# 01_MCU.net
KiCad netlist of a schematic drawn in Altium Designer
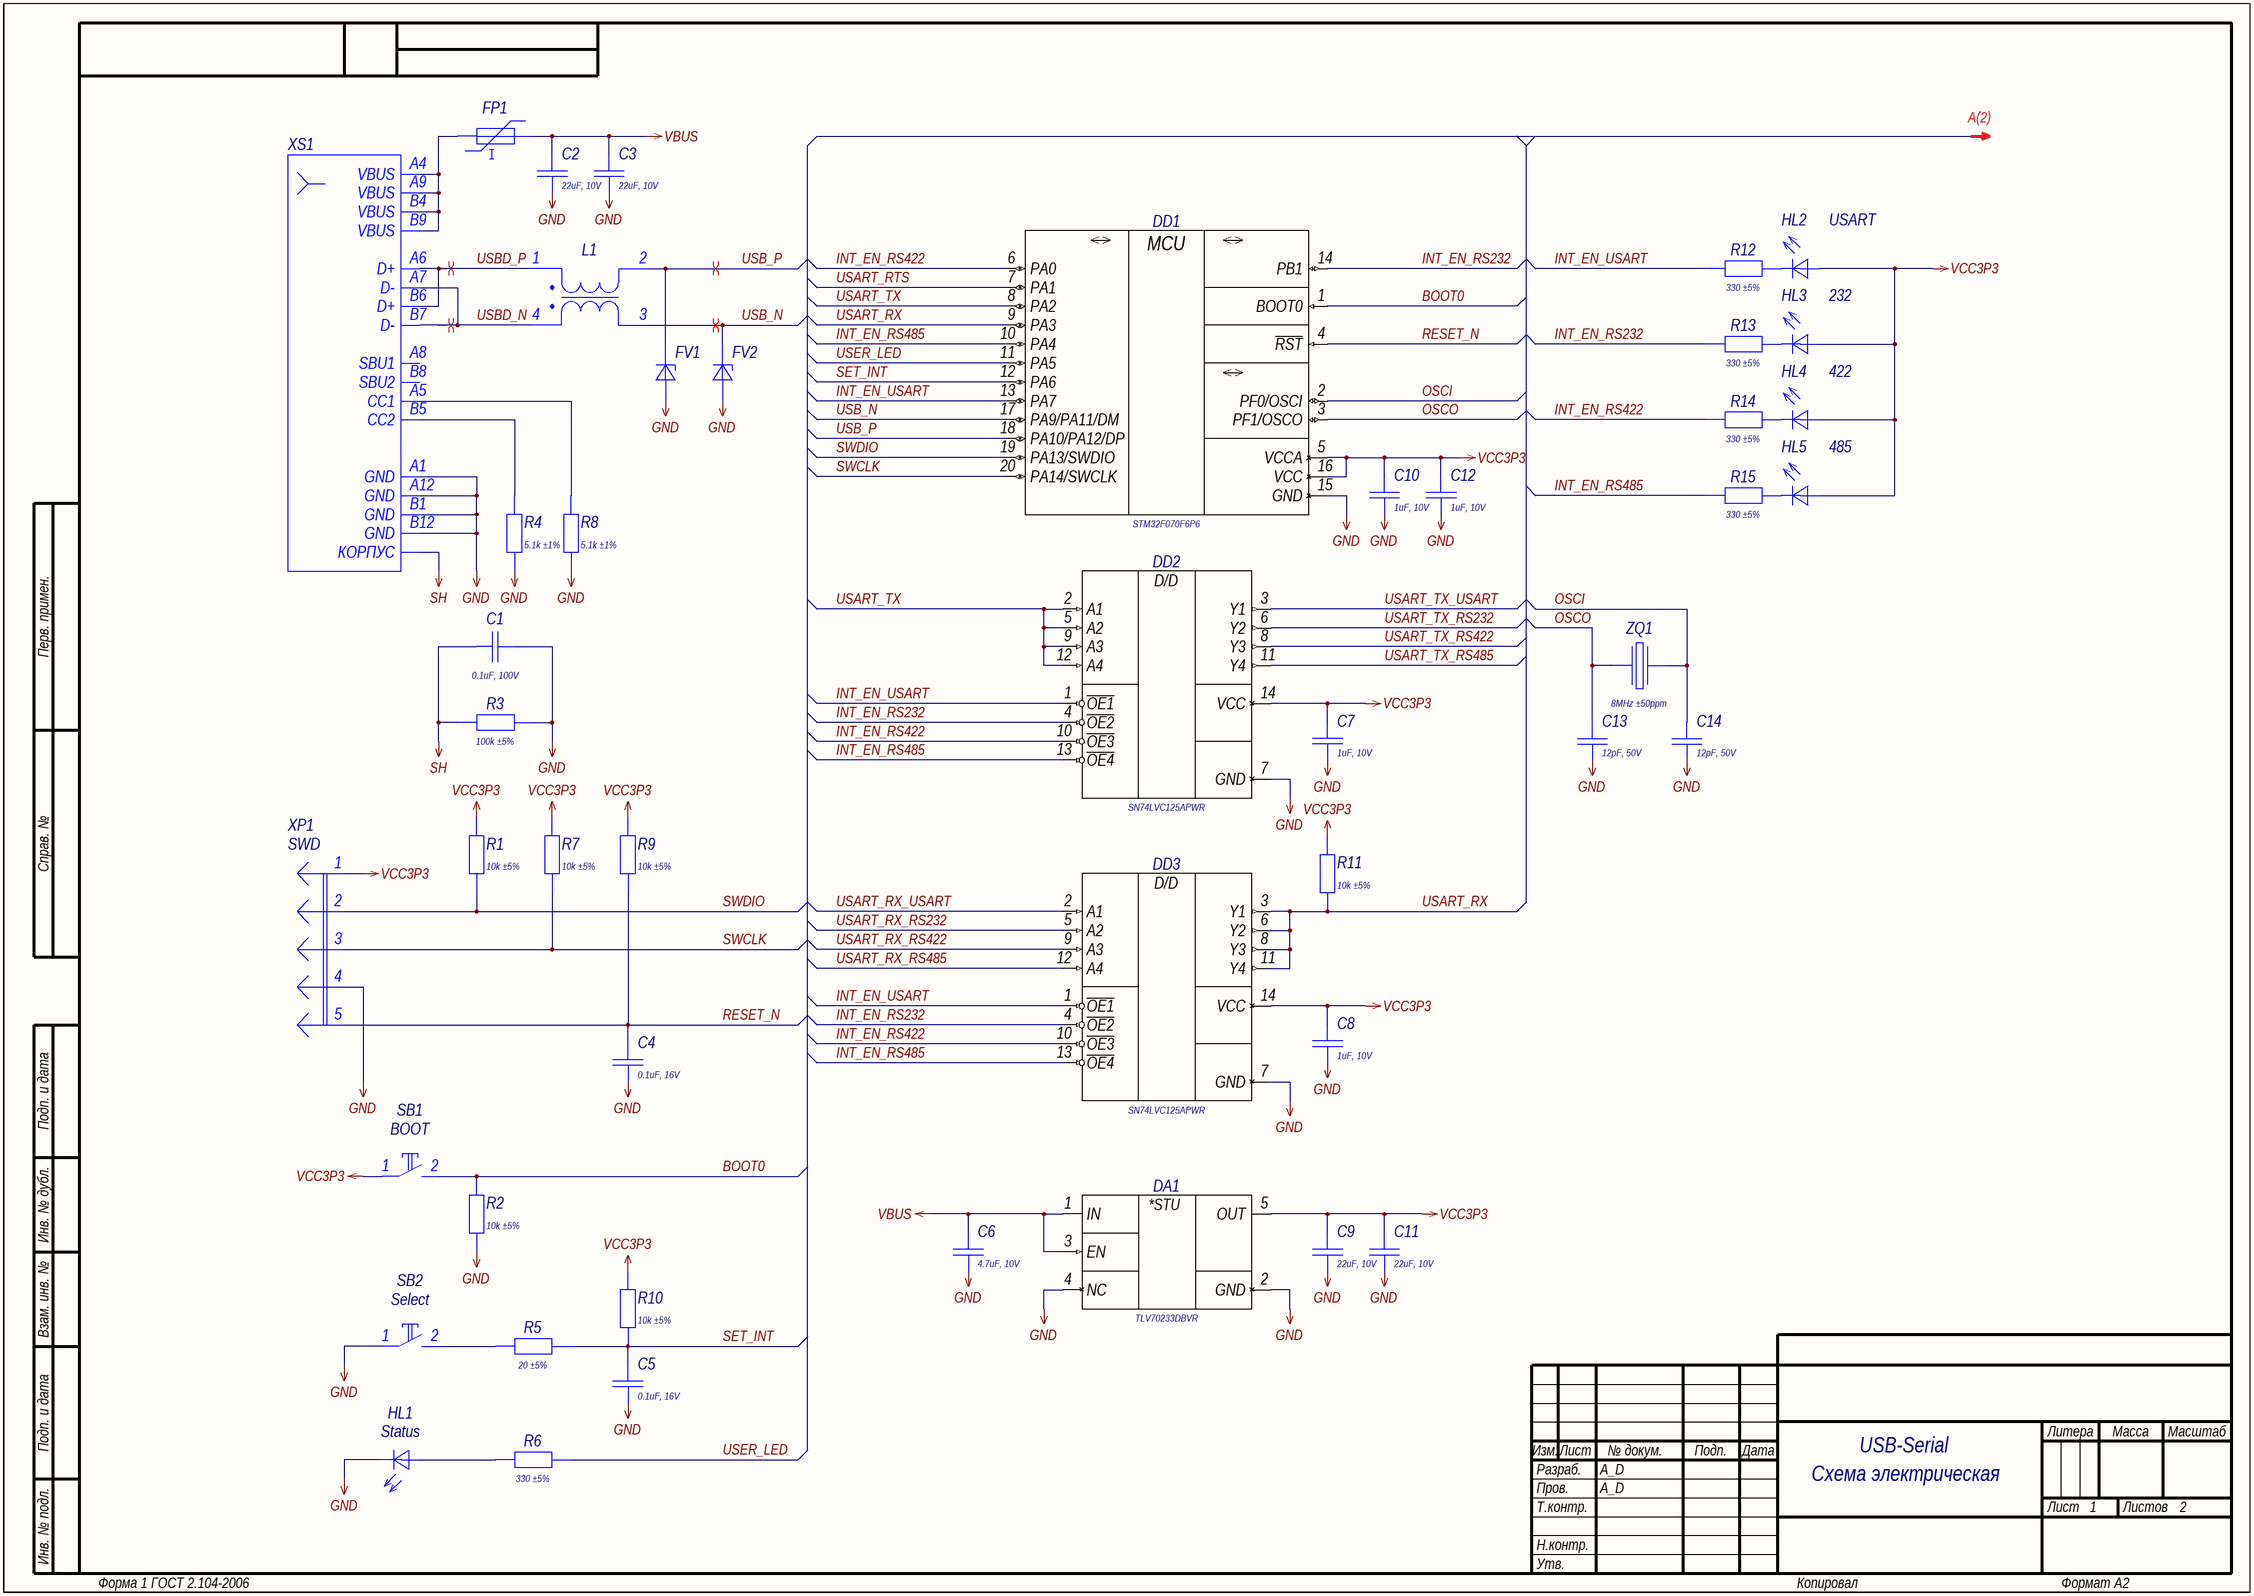
[diagram p0: 01_MCU.SchDoc]

(export (version "E")
  (design (tool "Eeschema 10.0.6"))
  (components
    (comp (ref "C1")
      (value "Capacitor")
      (footprint "C0603_160X080H080_H")
      (fields
        (field (name "SCHEMATIC VALUE") "0.1uF, 100V")
        (field (name "PART NUMBER") "GRM188R72A104KA35D")
        (field (name "VOLTAGE") "100V")
        (field (name "TOLERANCE") "±10%")
        (field (name "PUBLISHER") "Andrew Danich")
      )
      (libsource (lib "ADLib") (part "Capacitor"))
    )
    (comp (ref "C2")
      (value "Capacitor")
      (footprint "C0603_160X080H080_H")
      (fields
        (field (name "SCHEMATIC VALUE") "22uF, 10V")
        (field (name "PART NUMBER") "GRM188R61A226ME15D")
        (field (name "VOLTAGE") "10V")
        (field (name "TOLERANCE") "±20%")
        (field (name "PUBLISHER") "Andrew Danich")
      )
      (libsource (lib "ADLib") (part "Capacitor"))
    )
    (comp (ref "C3")
      (value "Capacitor")
      (footprint "C0603_160X080H080_H")
      (fields
        (field (name "SCHEMATIC VALUE") "22uF, 10V")
        (field (name "PART NUMBER") "GRM188R61A226ME15D")
        (field (name "VOLTAGE") "10V")
        (field (name "TOLERANCE") "±20%")
        (field (name "PUBLISHER") "Andrew Danich")
      )
      (libsource (lib "ADLib") (part "Capacitor"))
    )
    (comp (ref "C4")
      (value "Capacitor")
      (footprint "C0402_100X050H050_H")
      (fields
        (field (name "SCHEMATIC VALUE") "0.1uF, 16V")
        (field (name "PART NUMBER") "GCM155R71C104KA55D")
        (field (name "VOLTAGE") "16V")
        (field (name "TOLERANCE") "±10%")
        (field (name "PUBLISHER") "Andrew Danich")
      )
      (libsource (lib "ADLib") (part "Capacitor"))
    )
    (comp (ref "C5")
      (value "Capacitor")
      (footprint "C0402_100X050H050_H")
      (fields
        (field (name "SCHEMATIC VALUE") "0.1uF, 16V")
        (field (name "PART NUMBER") "GCM155R71C104KA55D")
        (field (name "VOLTAGE") "16V")
        (field (name "TOLERANCE") "±10%")
        (field (name "PUBLISHER") "Andrew Danich")
      )
      (libsource (lib "ADLib") (part "Capacitor"))
    )
    (comp (ref "C6")
      (value "Capacitor")
      (footprint "C0402_100X050H050_H")
      (fields
        (field (name "SCHEMATIC VALUE") "4.7uF, 10V")
        (field (name "PART NUMBER") "GRM155R61A475MEAAD")
        (field (name "VOLTAGE") "10V")
        (field (name "TOLERANCE") "±20%")
        (field (name "PUBLISHER") "Andrew Danich")
      )
      (libsource (lib "ADLib") (part "Capacitor"))
    )
    (comp (ref "C7")
      (value "Capacitor")
      (footprint "C0402_100X050H050_H")
      (fields
        (field (name "SCHEMATIC VALUE") "1uF, 10V")
        (field (name "PART NUMBER") "GRM155C71A105KE11D")
        (field (name "VOLTAGE") "10V")
        (field (name "TOLERANCE") "±10%")
        (field (name "PUBLISHER") "Andrew Danich")
      )
      (libsource (lib "ADLib") (part "Capacitor"))
    )
    (comp (ref "C8")
      (value "Capacitor")
      (footprint "C0402_100X050H050_H")
      (fields
        (field (name "SCHEMATIC VALUE") "1uF, 10V")
        (field (name "PART NUMBER") "GRM155C71A105KE11D")
        (field (name "VOLTAGE") "10V")
        (field (name "TOLERANCE") "±10%")
        (field (name "PUBLISHER") "Andrew Danich")
      )
      (libsource (lib "ADLib") (part "Capacitor"))
    )
    (comp (ref "C9")
      (value "Capacitor")
      (footprint "C0603_160X080H080_H")
      (fields
        (field (name "SCHEMATIC VALUE") "22uF, 10V")
        (field (name "PART NUMBER") "GRM188R61A226ME15D")
        (field (name "VOLTAGE") "10V")
        (field (name "TOLERANCE") "±20%")
        (field (name "PUBLISHER") "Andrew Danich")
      )
      (libsource (lib "ADLib") (part "Capacitor"))
    )
    (comp (ref "C10")
      (value "Capacitor")
      (footprint "C0402_100X050H050_H")
      (fields
        (field (name "SCHEMATIC VALUE") "1uF, 10V")
        (field (name "PART NUMBER") "GRM155C71A105KE11D")
        (field (name "VOLTAGE") "10V")
        (field (name "TOLERANCE") "±10%")
        (field (name "PUBLISHER") "Andrew Danich")
      )
      (libsource (lib "ADLib") (part "Capacitor"))
    )
    (comp (ref "C11")
      (value "Capacitor")
      (footprint "C0603_160X080H080_H")
      (fields
        (field (name "SCHEMATIC VALUE") "22uF, 10V")
        (field (name "PART NUMBER") "GRM188R61A226ME15D")
        (field (name "VOLTAGE") "10V")
        (field (name "TOLERANCE") "±20%")
        (field (name "PUBLISHER") "Andrew Danich")
      )
      (libsource (lib "ADLib") (part "Capacitor"))
    )
    (comp (ref "C12")
      (value "Capacitor")
      (footprint "C0402_100X050H050_H")
      (fields
        (field (name "SCHEMATIC VALUE") "1uF, 10V")
        (field (name "PART NUMBER") "GRM155C71A105KE11D")
        (field (name "VOLTAGE") "10V")
        (field (name "TOLERANCE") "±10%")
        (field (name "PUBLISHER") "Andrew Danich")
      )
      (libsource (lib "ADLib") (part "Capacitor"))
    )
    (comp (ref "C13")
      (value "Capacitor")
      (footprint "C0402_100X050H050_H")
      (fields
        (field (name "SCHEMATIC VALUE") "12pF, 50V")
        (field (name "PART NUMBER") "GRM1555C1H120JA01D")
        (field (name "VOLTAGE") "50V")
        (field (name "TOLERANCE") "±5%")
        (field (name "PUBLISHER") "Andrew Danich")
      )
      (libsource (lib "ADLib") (part "Capacitor"))
    )
    (comp (ref "C14")
      (value "Capacitor")
      (footprint "C0402_100X050H050_H")
      (fields
        (field (name "SCHEMATIC VALUE") "12pF, 50V")
        (field (name "PART NUMBER") "GRM1555C1H120JA01D")
        (field (name "VOLTAGE") "50V")
        (field (name "TOLERANCE") "±5%")
        (field (name "PUBLISHER") "Andrew Danich")
      )
      (libsource (lib "ADLib") (part "Capacitor"))
    )
    (comp (ref "DA1")
      (value "TLV702xxPDBV-Series")
      (footprint "SOT-23-5_095P290X160X145_N")
      (fields
        (field (name "SCHEMATIC VALUE") "TLV70233DBVR")
        (field (name "PART NUMBER") "TLV70233DBVR")
        (field (name "LCSC PART") "C26833")
        (field (name "MANUFACTURER") "Texas Instruments")
        (field (name "PUBLISHER") "Andrew Danich")
      )
      (libsource (lib "ADLib") (part "TLV702xxPDBV-Series"))
    )
    (comp (ref "DD1")
      (value "STM32F070FxPx-Series")
      (footprint "TSSOP-20_065P650X440X120_N")
      (fields
        (field (name "SCHEMATIC VALUE") "STM32F070F6P6")
        (field (name "PART NUMBER") "STM32F070F6P6")
        (field (name "MANUFACTURER") "STMicroelectronics")
        (field (name "PUBLISHER") "Andrew Danich")
      )
      (libsource (lib "ADLib") (part "STM32F070FxPx-Series"))
    )
    (comp (ref "DD2")
      (value "SN74LVC125APW")
      (footprint "TSSOP-14_065P500X440X120_N")
      (fields
        (field (name "SCHEMATIC VALUE") "SN74LVC125APWR")
        (field (name "PART NUMBER") "SN74LVC125APWR")
        (field (name "LCSC PART") "C7813")
        (field (name "MANUFACTURER") "Texas Instruments")
        (field (name "PUBLISHER") "Andrew Danich")
      )
      (libsource (lib "ADLib") (part "SN74LVC125APW"))
    )
    (comp (ref "DD3")
      (value "SN74LVC125APW")
      (footprint "TSSOP-14_065P500X440X120_N")
      (fields
        (field (name "SCHEMATIC VALUE") "SN74LVC125APWR")
        (field (name "PART NUMBER") "SN74LVC125APWR")
        (field (name "LCSC PART") "C7813")
        (field (name "MANUFACTURER") "Texas Instruments")
        (field (name "PUBLISHER") "Andrew Danich")
      )
      (libsource (lib "ADLib") (part "SN74LVC125APW"))
    )
    (comp (ref "FP1")
      (value "Fuse_PTC")
      (footprint "F0603_160X080H075_H")
      (fields (field (name "PART NUMBER") "0603L100SLYR") (field (name "MANUFACTURER") "Littelfuse"))
      (libsource (lib "ADLib") (part "Fuse_PTC"))
    )
    (comp (ref "FV1")
      (value "Suppressor_21")
      (footprint "X1-DFN1006-2_070P060X100X050_N")
      (fields
        (field (name "PART NUMBER") "PESDUC2FD5VU")
        (field (name "LCSC PART") "C496534")
        (field (name "MANUFACTURER") "Shanghai Prisemi Elec")
        (field (name "PUBLISHER") "Andrew Danich")
      )
      (libsource (lib "ADLib") (part "Suppressor_21"))
    )
    (comp (ref "FV2")
      (value "Suppressor_21")
      (footprint "X1-DFN1006-2_070P060X100X050_N")
      (fields
        (field (name "PART NUMBER") "PESDUC2FD5VU")
        (field (name "LCSC PART") "C496534")
        (field (name "MANUFACTURER") "Shanghai Prisemi Elec")
        (field (name "PUBLISHER") "Andrew Danich")
      )
      (libsource (lib "ADLib") (part "Suppressor_21"))
    )
    (comp (ref "HL1")
      (value "Status")
      (footprint "LD0603_L")
      (fields
        (field (name "PART NUMBER") "NCD0603G1")
        (field (name "MANUFACTURER") "Foshan NationStar Optoelectronics")
        (field (name "LCSC PART") "C84267")
        (field (name "PUBLISHER") "Andrew Danich")
      )
      (libsource (lib "ADLib") (part "Led-1"))
    )
    (comp (ref "HL2")
      (value "USART")
      (footprint "LD0603_L")
      (fields
        (field (name "PART NUMBER") "NCD0603W1")
        (field (name "MANUFACTURER") "Foshan NationStar Optoelectronics")
        (field (name "LCSC PART") "C84265")
        (field (name "PUBLISHER") "Andrew Danich")
      )
      (libsource (lib "ADLib") (part "Led-1"))
    )
    (comp (ref "HL3")
      (value "232")
      (footprint "LD0603_L")
      (fields
        (field (name "PART NUMBER") "NCD0603W1")
        (field (name "MANUFACTURER") "Foshan NationStar Optoelectronics")
        (field (name "LCSC PART") "C84265")
        (field (name "PUBLISHER") "Andrew Danich")
      )
      (libsource (lib "ADLib") (part "Led-1"))
    )
    (comp (ref "HL4")
      (value "422")
      (footprint "LD0603_L")
      (fields
        (field (name "PART NUMBER") "NCD0603W1")
        (field (name "MANUFACTURER") "Foshan NationStar Optoelectronics")
        (field (name "LCSC PART") "C84265")
        (field (name "PUBLISHER") "Andrew Danich")
      )
      (libsource (lib "ADLib") (part "Led-1"))
    )
    (comp (ref "HL5")
      (value "485")
      (footprint "LD0603_L")
      (fields
        (field (name "PART NUMBER") "NCD0603W1")
        (field (name "MANUFACTURER") "Foshan NationStar Optoelectronics")
        (field (name "LCSC PART") "C84265")
        (field (name "PUBLISHER") "Andrew Danich")
      )
      (libsource (lib "ADLib") (part "Led-1"))
    )
    (comp (ref "L1")
      (value "Coil-2xCommon_H")
      (footprint "DLW21HN-Series")
      (fields
        (field (name "PART NUMBER") "DLW21HN121SQ2L")
        (field (name "MANUFACTURER") "Murata")
        (field (name "PUBLISHER") "Andrew Danich")
      )
      (libsource (lib "ADLib") (part "Coil-2xCommon_H"))
    )
    (comp (ref "R1")
      (value "Resistor")
      (footprint "R0402_100X050H035_H")
      (fields
        (field (name "SCHEMATIC VALUE") "10k ±5%")
        (field (name "PART NUMBER") "RC0402JR-0710KL")
        (field (name "TOLERANCE") "±5%")
        (field (name "MANUFACTURER") "Yageo")
        (field (name "PUBLISHER") "Andrew Danich")
      )
      (libsource (lib "ADLib") (part "Resistor"))
    )
    (comp (ref "R2")
      (value "Resistor")
      (footprint "R0402_100X050H035_H")
      (fields
        (field (name "SCHEMATIC VALUE") "10k ±5%")
        (field (name "PART NUMBER") "RC0402JR-0710KL")
        (field (name "TOLERANCE") "±5%")
        (field (name "MANUFACTURER") "Yageo")
        (field (name "PUBLISHER") "Andrew Danich")
      )
      (libsource (lib "ADLib") (part "Resistor"))
    )
    (comp (ref "R3")
      (value "Resistor")
      (footprint "R0402_100X050H035_H")
      (fields
        (field (name "SCHEMATIC VALUE") "100k ±5%")
        (field (name "PART NUMBER") "RC0402JR-07100KL")
        (field (name "TOLERANCE") "±5%")
        (field (name "MANUFACTURER") "Yageo")
        (field (name "PUBLISHER") "Andrew Danich")
      )
      (libsource (lib "ADLib") (part "Resistor"))
    )
    (comp (ref "R4")
      (value "Resistor")
      (footprint "R0402_100X050H035_H")
      (fields
        (field (name "SCHEMATIC VALUE") "5.1k ±1%")
        (field (name "PART NUMBER") "RC0402FR-075K1L")
        (field (name "TOLERANCE") "±1%")
        (field (name "MANUFACTURER") "Yageo")
        (field (name "PUBLISHER") "Andrew Danich")
      )
      (libsource (lib "ADLib") (part "Resistor"))
    )
    (comp (ref "R5")
      (value "Resistor")
      (footprint "R0402_100X050H035_H")
      (fields
        (field (name "SCHEMATIC VALUE") "20 ±5%")
        (field (name "PART NUMBER") "RC0402JR-0720RL")
        (field (name "TOLERANCE") "±5%")
        (field (name "MANUFACTURER") "Yageo")
        (field (name "PUBLISHER") "Andrew Danich")
      )
      (libsource (lib "ADLib") (part "Resistor"))
    )
    (comp (ref "R6")
      (value "Resistor")
      (footprint "R0402_100X050H035_H")
      (fields
        (field (name "SCHEMATIC VALUE") "330 ±5%")
        (field (name "PART NUMBER") "RC0402JR-07330RL")
        (field (name "TOLERANCE") "±5%")
        (field (name "MANUFACTURER") "Yageo")
        (field (name "PUBLISHER") "Andrew Danich")
      )
      (libsource (lib "ADLib") (part "Resistor"))
    )
    (comp (ref "R7")
      (value "Resistor")
      (footprint "R0402_100X050H035_H")
      (fields
        (field (name "SCHEMATIC VALUE") "10k ±5%")
        (field (name "PART NUMBER") "RC0402JR-0710KL")
        (field (name "TOLERANCE") "±5%")
        (field (name "MANUFACTURER") "Yageo")
        (field (name "PUBLISHER") "Andrew Danich")
      )
      (libsource (lib "ADLib") (part "Resistor"))
    )
    (comp (ref "R8")
      (value "Resistor")
      (footprint "R0402_100X050H035_H")
      (fields
        (field (name "SCHEMATIC VALUE") "5.1k ±1%")
        (field (name "PART NUMBER") "RC0402FR-075K1L")
        (field (name "TOLERANCE") "±1%")
        (field (name "MANUFACTURER") "Yageo")
        (field (name "PUBLISHER") "Andrew Danich")
      )
      (libsource (lib "ADLib") (part "Resistor"))
    )
    (comp (ref "R9")
      (value "Resistor")
      (footprint "R0402_100X050H035_H")
      (fields
        (field (name "SCHEMATIC VALUE") "10k ±5%")
        (field (name "PART NUMBER") "RC0402JR-0710KL")
        (field (name "TOLERANCE") "±5%")
        (field (name "MANUFACTURER") "Yageo")
        (field (name "PUBLISHER") "Andrew Danich")
      )
      (libsource (lib "ADLib") (part "Resistor"))
    )
    (comp (ref "R10")
      (value "Resistor")
      (footprint "R0402_100X050H035_H")
      (fields
        (field (name "SCHEMATIC VALUE") "10k ±5%")
        (field (name "PART NUMBER") "RC0402JR-0710KL")
        (field (name "TOLERANCE") "±5%")
        (field (name "MANUFACTURER") "Yageo")
        (field (name "PUBLISHER") "Andrew Danich")
      )
      (libsource (lib "ADLib") (part "Resistor"))
    )
    (comp (ref "R11")
      (value "Resistor")
      (footprint "R0402_100X050H035_H")
      (fields
        (field (name "SCHEMATIC VALUE") "10k ±5%")
        (field (name "PART NUMBER") "RC0402JR-0710KL")
        (field (name "TOLERANCE") "±5%")
        (field (name "MANUFACTURER") "Yageo")
        (field (name "PUBLISHER") "Andrew Danich")
      )
      (libsource (lib "ADLib") (part "Resistor"))
    )
    (comp (ref "R12")
      (value "Resistor")
      (footprint "R0402_100X050H035_H")
      (fields
        (field (name "SCHEMATIC VALUE") "330 ±5%")
        (field (name "PART NUMBER") "RC0402JR-07330RL")
        (field (name "TOLERANCE") "±5%")
        (field (name "MANUFACTURER") "Yageo")
        (field (name "PUBLISHER") "Andrew Danich")
      )
      (libsource (lib "ADLib") (part "Resistor"))
    )
    (comp (ref "R13")
      (value "Resistor")
      (footprint "R0402_100X050H035_H")
      (fields
        (field (name "SCHEMATIC VALUE") "330 ±5%")
        (field (name "PART NUMBER") "RC0402JR-07330RL")
        (field (name "TOLERANCE") "±5%")
        (field (name "MANUFACTURER") "Yageo")
        (field (name "PUBLISHER") "Andrew Danich")
      )
      (libsource (lib "ADLib") (part "Resistor"))
    )
    (comp (ref "R14")
      (value "Resistor")
      (footprint "R0402_100X050H035_H")
      (fields
        (field (name "SCHEMATIC VALUE") "330 ±5%")
        (field (name "PART NUMBER") "RC0402JR-07330RL")
        (field (name "TOLERANCE") "±5%")
        (field (name "MANUFACTURER") "Yageo")
        (field (name "PUBLISHER") "Andrew Danich")
      )
      (libsource (lib "ADLib") (part "Resistor"))
    )
    (comp (ref "R15")
      (value "Resistor")
      (footprint "R0402_100X050H035_H")
      (fields
        (field (name "SCHEMATIC VALUE") "330 ±5%")
        (field (name "PART NUMBER") "RC0402JR-07330RL")
        (field (name "TOLERANCE") "±5%")
        (field (name "MANUFACTURER") "Yageo")
        (field (name "PUBLISHER") "Andrew Danich")
      )
      (libsource (lib "ADLib") (part "Resistor"))
    )
    (comp (ref "SB1")
      (value "BOOT")
      (footprint "IT-1185AP")
      (fields (field (name "PART NUMBER") "IT-1185AP") (field (name "PUBLISHER") "Andrew Danich"))
      (libsource (lib "ADLib") (part "BT-01x-01p"))
    )
    (comp (ref "SB2")
      (value "Select")
      (footprint "IT-1185AP")
      (fields (field (name "PART NUMBER") "IT-1185AP") (field (name "PUBLISHER") "Andrew Danich"))
      (libsource (lib "ADLib") (part "BT-01x-01p"))
    )
    (comp (ref "XP1")
      (value "SWD")
      (footprint "PLS-5")
      (fields (field (name "PART NUMBER") "PLS-5") (field (name "PUBLISHER") "Andrew Danich"))
      (libsource (lib "ADLib") (part "Con-5-M"))
    )
    (comp (ref "XS1")
      (value "Text")
      (footprint "U262-161N-4BVC11")
      (fields
        (field (name "PART NUMBER") "U262-161N-4BVC11")
        (field (name "MANUFACTURER") "XKB Enterprise")
        (field (name "PUBLISHER") "Andrew Danich")
      )
      (libsource (lib "ADLib") (part "Con-USB_C-F-16P"))
    )
    (comp (ref "ZQ1")
      (value "Crystal")
      (footprint "SMD 5x3.2mm")
      (fields
        (field (name "SCHEMATIC VALUE") "8MHz ±50ppm")
        (field (name "PART NUMBER") "KX-9A 8.0 MHz 30/50/100 16 pF")
        (field (name "MANUFACTURER") "Geyer")
        (field (name "PUBLISHER") "Andrew Danich")
      )
      (libsource (lib "ADLib") (part "Crystal"))
    )
  )
  (nets
    (net (code "1") (name "/BOOT0") (class "Default")
      (node (ref "DD1") (pin "1") (pinfunction "BOOT0_1") (pintype "input"))
      (node (ref "R2") (pin "2") (pinfunction "2_2") (pintype "passive"))
      (node (ref "SB1") (pin "2") (pintype "passive"))
    )
    (net (code "2") (name "/INT_EN_RS232") (class "Default")
      (node (ref "DD1") (pin "14") (pinfunction "PB1_14") (pintype "bidirectional"))
      (node (ref "DD2") (pin "4") (pinfunction "~{OE2}_4") (pintype "input"))
      (node (ref "DD3") (pin "4") (pinfunction "~{OE2}_4") (pintype "input"))
      (node (ref "R13") (pin "2") (pinfunction "2_2") (pintype "passive"))
    )
    (net (code "3") (name "/INT_EN_RS422") (class "Default")
      (node (ref "DD1") (pin "6") (pinfunction "PA0_6") (pintype "bidirectional"))
      (node (ref "DD2") (pin "10") (pinfunction "~{OE3}_10") (pintype "input"))
      (node (ref "DD3") (pin "10") (pinfunction "~{OE3}_10") (pintype "input"))
      (node (ref "R14") (pin "2") (pinfunction "2_2") (pintype "passive"))
    )
    (net (code "4") (name "/INT_EN_RS485") (class "Default")
      (node (ref "DD1") (pin "10") (pinfunction "PA4_10") (pintype "bidirectional"))
      (node (ref "DD2") (pin "13") (pinfunction "~{OE4}_13") (pintype "input"))
      (node (ref "DD3") (pin "13") (pinfunction "~{OE4}_13") (pintype "input"))
      (node (ref "R15") (pin "2") (pinfunction "2_2") (pintype "passive"))
    )
    (net (code "5") (name "/INT_EN_USART") (class "Default")
      (node (ref "DD1") (pin "13") (pinfunction "PA7_13") (pintype "bidirectional"))
      (node (ref "DD2") (pin "1") (pinfunction "~{OE1}_1") (pintype "input"))
      (node (ref "DD3") (pin "1") (pinfunction "~{OE1}_1") (pintype "input"))
      (node (ref "R12") (pin "2") (pinfunction "2_2") (pintype "passive"))
    )
    (net (code "6") (name "/OSCI") (class "Default")
      (node (ref "C14") (pin "2") (pinfunction "2_2") (pintype "passive"))
      (node (ref "DD1") (pin "2") (pinfunction "PF0/OSCI_2") (pintype "bidirectional"))
      (node (ref "ZQ1") (pin "3") (pinfunction "3_3") (pintype "passive"))
    )
    (net (code "7") (name "/OSCO") (class "Default")
      (node (ref "C13") (pin "2") (pinfunction "2_2") (pintype "passive"))
      (node (ref "DD1") (pin "3") (pinfunction "PF1/OSCO_3") (pintype "bidirectional"))
      (node (ref "ZQ1") (pin "1") (pinfunction "1_1") (pintype "passive"))
    )
    (net (code "8") (name "/RESET_N") (class "Default")
      (node (ref "C4") (pin "1") (pinfunction "1_1") (pintype "passive"))
      (node (ref "DD1") (pin "4") (pinfunction "~{RST}_4") (pintype "input"))
      (node (ref "R9") (pin "1") (pinfunction "1_1") (pintype "passive"))
      (node (ref "XP1") (pin "5") (pintype "passive"))
    )
    (net (code "9") (name "/SET_INT") (class "Default")
      (node (ref "C5") (pin "1") (pinfunction "1_1") (pintype "passive"))
      (node (ref "DD1") (pin "12") (pinfunction "PA6_12") (pintype "bidirectional"))
      (node (ref "R10") (pin "1") (pinfunction "1_1") (pintype "passive"))
      (node (ref "R5") (pin "1") (pinfunction "1_1") (pintype "passive"))
    )
    (net (code "10") (name "/SWCLK") (class "Default")
      (node (ref "DD1") (pin "20") (pinfunction "PA14/SWCLK_20") (pintype "bidirectional"))
      (node (ref "R7") (pin "1") (pinfunction "1_1") (pintype "passive"))
      (node (ref "XP1") (pin "3") (pintype "passive"))
    )
    (net (code "11") (name "/SWDIO") (class "Default")
      (node (ref "DD1") (pin "19") (pinfunction "PA13/SWDIO_19") (pintype "bidirectional"))
      (node (ref "R1") (pin "1") (pinfunction "1_1") (pintype "passive"))
      (node (ref "XP1") (pin "2") (pintype "passive"))
    )
    (net (code "12") (name "/USART_RTS") (class "Default")
      (node (ref "DD1") (pin "7") (pinfunction "PA1_7") (pintype "bidirectional"))
    )
    (net (code "13") (name "/USART_RX") (class "Default")
      (node (ref "DD1") (pin "9") (pinfunction "PA3_9") (pintype "bidirectional"))
      (node (ref "DD3") (pin "11") (pinfunction "Y4_11") (pintype "output"))
      (node (ref "DD3") (pin "3") (pinfunction "Y1_3") (pintype "output"))
      (node (ref "DD3") (pin "6") (pinfunction "Y2_6") (pintype "output"))
      (node (ref "DD3") (pin "8") (pinfunction "Y3_8") (pintype "output"))
      (node (ref "R11") (pin "1") (pinfunction "1_1") (pintype "passive"))
    )
    (net (code "14") (name "/USART_RX_RS232") (class "Default")
      (node (ref "DD3") (pin "5") (pinfunction "A2_5") (pintype "input"))
    )
    (net (code "15") (name "/USART_RX_RS422") (class "Default")
      (node (ref "DD3") (pin "9") (pinfunction "A3_9") (pintype "input"))
    )
    (net (code "16") (name "/USART_RX_RS485") (class "Default")
      (node (ref "DD3") (pin "12") (pinfunction "A4_12") (pintype "input"))
    )
    (net (code "17") (name "/USART_RX_USART") (class "Default")
      (node (ref "DD3") (pin "2") (pinfunction "A1_2") (pintype "input"))
    )
    (net (code "18") (name "/USART_TX") (class "Default")
      (node (ref "DD1") (pin "8") (pinfunction "PA2_8") (pintype "bidirectional"))
      (node (ref "DD2") (pin "12") (pinfunction "A4_12") (pintype "input"))
      (node (ref "DD2") (pin "2") (pinfunction "A1_2") (pintype "input"))
      (node (ref "DD2") (pin "5") (pinfunction "A2_5") (pintype "input"))
      (node (ref "DD2") (pin "9") (pinfunction "A3_9") (pintype "input"))
    )
    (net (code "19") (name "/USART_TX_RS232") (class "Default")
      (node (ref "DD2") (pin "6") (pinfunction "Y2_6") (pintype "output"))
    )
    (net (code "20") (name "/USART_TX_RS422") (class "Default")
      (node (ref "DD2") (pin "8") (pinfunction "Y3_8") (pintype "output"))
    )
    (net (code "21") (name "/USART_TX_RS485") (class "Default")
      (node (ref "DD2") (pin "11") (pinfunction "Y4_11") (pintype "output"))
    )
    (net (code "22") (name "/USART_TX_USART") (class "Default")
      (node (ref "DD2") (pin "3") (pinfunction "Y1_3") (pintype "output"))
    )
    (net (code "23") (name "/USBD_N") (class "Default")
      (node (ref "L1") (pin "4") (pinfunction "4_4") (pintype "passive"))
      (node (ref "XS1") (pin "A7") (pinfunction "D-_A7") (pintype "passive"))
      (node (ref "XS1") (pin "B7") (pinfunction "D-_B7") (pintype "passive"))
    )
    (net (code "24") (name "/USBD_P") (class "Default")
      (node (ref "L1") (pin "1") (pinfunction "1_1") (pintype "passive"))
      (node (ref "XS1") (pin "A6") (pinfunction "D+_A6") (pintype "passive"))
      (node (ref "XS1") (pin "B6") (pinfunction "D+_B6") (pintype "passive"))
    )
    (net (code "25") (name "/USB_N") (class "Default")
      (node (ref "DD1") (pin "17") (pinfunction "PA9/PA11/DM_17") (pintype "bidirectional"))
      (node (ref "FV2") (pin "1") (pinfunction "К_1") (pintype "passive"))
      (node (ref "L1") (pin "3") (pinfunction "3_3") (pintype "passive"))
    )
    (net (code "26") (name "/USB_P") (class "Default")
      (node (ref "DD1") (pin "18") (pinfunction "PA10/PA12/DP_18") (pintype "bidirectional"))
      (node (ref "FV1") (pin "1") (pinfunction "К_1") (pintype "passive"))
      (node (ref "L1") (pin "2") (pinfunction "2_2") (pintype "passive"))
    )
    (net (code "27") (name "/USER_LED") (class "Default")
      (node (ref "DD1") (pin "11") (pinfunction "PA5_11") (pintype "bidirectional"))
      (node (ref "R6") (pin "1") (pinfunction "1_1") (pintype "passive"))
    )
    (net (code "28") (name "GND") (class "Default")
      (node (ref "C1") (pin "1") (pinfunction "1_1") (pintype "passive"))
      (node (ref "C10") (pin "2") (pinfunction "2_2") (pintype "passive"))
      (node (ref "C11") (pin "1") (pinfunction "1_1") (pintype "passive"))
      (node (ref "C12") (pin "2") (pinfunction "2_2") (pintype "passive"))
      (node (ref "C13") (pin "1") (pinfunction "1_1") (pintype "passive"))
      (node (ref "C14") (pin "1") (pinfunction "1_1") (pintype "passive"))
      (node (ref "C2") (pin "2") (pinfunction "2_2") (pintype "passive"))
      (node (ref "C3") (pin "2") (pinfunction "2_2") (pintype "passive"))
      (node (ref "C4") (pin "2") (pinfunction "2_2") (pintype "passive"))
      (node (ref "C5") (pin "2") (pinfunction "2_2") (pintype "passive"))
      (node (ref "C6") (pin "1") (pinfunction "1_1") (pintype "passive"))
      (node (ref "C7") (pin "2") (pinfunction "2_2") (pintype "passive"))
      (node (ref "C8") (pin "2") (pinfunction "2_2") (pintype "passive"))
      (node (ref "C9") (pin "1") (pinfunction "1_1") (pintype "passive"))
      (node (ref "DA1") (pin "2") (pinfunction "GND_2") (pintype "power_in"))
      (node (ref "DA1") (pin "4") (pinfunction "NC_4") (pintype "passive"))
      (node (ref "DD1") (pin "15") (pinfunction "GND_15") (pintype "power_in"))
      (node (ref "DD2") (pin "7") (pinfunction "GND_7") (pintype "power_in"))
      (node (ref "DD3") (pin "7") (pinfunction "GND_7") (pintype "power_in"))
      (node (ref "FV1") (pin "2") (pinfunction "А_2") (pintype "passive"))
      (node (ref "FV2") (pin "2") (pinfunction "А_2") (pintype "passive"))
      (node (ref "HL1") (pin "2") (pintype "passive"))
      (node (ref "R2") (pin "1") (pinfunction "1_1") (pintype "passive"))
      (node (ref "R3") (pin "1") (pinfunction "1_1") (pintype "passive"))
      (node (ref "R4") (pin "1") (pinfunction "1_1") (pintype "passive"))
      (node (ref "R8") (pin "1") (pinfunction "1_1") (pintype "passive"))
      (node (ref "SB2") (pin "1") (pintype "passive"))
      (node (ref "XP1") (pin "4") (pintype "passive"))
      (node (ref "XS1") (pin "A1") (pinfunction "GND_A1") (pintype "passive"))
      (node (ref "XS1") (pin "A12") (pinfunction "GND_A12") (pintype "passive"))
      (node (ref "XS1") (pin "B1") (pinfunction "GND_B1") (pintype "passive"))
      (node (ref "XS1") (pin "B12") (pinfunction "GND_B12") (pintype "passive"))
    )
    (net (code "29") (name "Net-(FP1-Pad1)") (class "Default")
      (node (ref "FP1") (pin "1") (pinfunction "1_1") (pintype "passive"))
      (node (ref "XS1") (pin "A4") (pinfunction "VBUS_A4") (pintype "passive"))
      (node (ref "XS1") (pin "A9") (pinfunction "VBUS_A9") (pintype "passive"))
      (node (ref "XS1") (pin "B4") (pinfunction "VBUS_B4") (pintype "passive"))
      (node (ref "XS1") (pin "B9") (pinfunction "VBUS_B9") (pintype "passive"))
    )
    (net (code "30") (name "Net-(HL1-Pad1)") (class "Default")
      (node (ref "HL1") (pin "1") (pintype "passive"))
      (node (ref "R6") (pin "2") (pinfunction "2_2") (pintype "passive"))
    )
    (net (code "31") (name "Net-(HL2-Pad2)") (class "Default")
      (node (ref "HL2") (pin "2") (pintype "passive"))
      (node (ref "R12") (pin "1") (pinfunction "1_1") (pintype "passive"))
    )
    (net (code "32") (name "Net-(HL3-Pad2)") (class "Default")
      (node (ref "HL3") (pin "2") (pintype "passive"))
      (node (ref "R13") (pin "1") (pinfunction "1_1") (pintype "passive"))
    )
    (net (code "33") (name "Net-(HL4-Pad2)") (class "Default")
      (node (ref "HL4") (pin "2") (pintype "passive"))
      (node (ref "R14") (pin "1") (pinfunction "1_1") (pintype "passive"))
    )
    (net (code "34") (name "Net-(HL5-Pad2)") (class "Default")
      (node (ref "HL5") (pin "2") (pintype "passive"))
      (node (ref "R15") (pin "1") (pinfunction "1_1") (pintype "passive"))
    )
    (net (code "35") (name "Net-(R5-Pad2)") (class "Default")
      (node (ref "R5") (pin "2") (pinfunction "2_2") (pintype "passive"))
      (node (ref "SB2") (pin "2") (pintype "passive"))
    )
    (net (code "36") (name "Net-(XS1-CC1)") (class "Default")
      (node (ref "R8") (pin "2") (pinfunction "2_2") (pintype "passive"))
      (node (ref "XS1") (pin "A5") (pinfunction "CC1_A5") (pintype "passive"))
    )
    (net (code "37") (name "Net-(XS1-CC2)") (class "Default")
      (node (ref "R4") (pin "2") (pinfunction "2_2") (pintype "passive"))
      (node (ref "XS1") (pin "B5") (pinfunction "CC2_B5") (pintype "passive"))
    )
    (net (code "38") (name "SH") (class "Default")
      (node (ref "C1") (pin "2") (pinfunction "2_2") (pintype "passive"))
      (node (ref "R3") (pin "2") (pinfunction "2_2") (pintype "passive"))
      (node (ref "XS1") (pin "SH") (pinfunction "КОРПУС_SH") (pintype "passive"))
    )
    (net (code "39") (name "VBUS") (class "Default")
      (node (ref "C2") (pin "1") (pinfunction "1_1") (pintype "passive"))
      (node (ref "C3") (pin "1") (pinfunction "1_1") (pintype "passive"))
      (node (ref "C6") (pin "2") (pinfunction "2_2") (pintype "passive"))
      (node (ref "DA1") (pin "1") (pinfunction "IN_1") (pintype "power_in"))
      (node (ref "DA1") (pin "3") (pinfunction "EN_3") (pintype "input"))
      (node (ref "FP1") (pin "2") (pinfunction "2_2") (pintype "passive"))
    )
    (net (code "40") (name "VCC3P3") (class "Default")
      (node (ref "C10") (pin "1") (pinfunction "1_1") (pintype "passive"))
      (node (ref "C11") (pin "2") (pinfunction "2_2") (pintype "passive"))
      (node (ref "C12") (pin "1") (pinfunction "1_1") (pintype "passive"))
      (node (ref "C7") (pin "1") (pinfunction "1_1") (pintype "passive"))
      (node (ref "C8") (pin "1") (pinfunction "1_1") (pintype "passive"))
      (node (ref "C9") (pin "2") (pinfunction "2_2") (pintype "passive"))
      (node (ref "DA1") (pin "5") (pinfunction "OUT_5") (pintype "power_in"))
      (node (ref "DD1") (pin "16") (pinfunction "VCC_16") (pintype "power_in"))
      (node (ref "DD1") (pin "5") (pinfunction "VCCA_5") (pintype "power_in"))
      (node (ref "DD2") (pin "14") (pinfunction "VCC_14") (pintype "power_in"))
      (node (ref "DD3") (pin "14") (pinfunction "VCC_14") (pintype "power_in"))
      (node (ref "HL2") (pin "1") (pintype "passive"))
      (node (ref "HL3") (pin "1") (pintype "passive"))
      (node (ref "HL4") (pin "1") (pintype "passive"))
      (node (ref "HL5") (pin "1") (pintype "passive"))
      (node (ref "R1") (pin "2") (pinfunction "2_2") (pintype "passive"))
      (node (ref "R10") (pin "2") (pinfunction "2_2") (pintype "passive"))
      (node (ref "R11") (pin "2") (pinfunction "2_2") (pintype "passive"))
      (node (ref "R7") (pin "2") (pinfunction "2_2") (pintype "passive"))
      (node (ref "R9") (pin "2") (pinfunction "2_2") (pintype "passive"))
      (node (ref "SB1") (pin "1") (pintype "passive"))
      (node (ref "XP1") (pin "1") (pintype "passive"))
    )
    (net (code "41") (name "unconnected-(XS1-SBU1-PadA8)") (class "Default")
      (node (ref "XS1") (pin "A8") (pinfunction "SBU1_A8") (pintype "passive"))
    )
    (net (code "42") (name "unconnected-(XS1-SBU2-PadB8)") (class "Default")
      (node (ref "XS1") (pin "B8") (pinfunction "SBU2_B8") (pintype "passive"))
    )
  )
)
